# Stepping_Motor_DriverB.net
KiCad netlist of a schematic drawn in Altium Designer
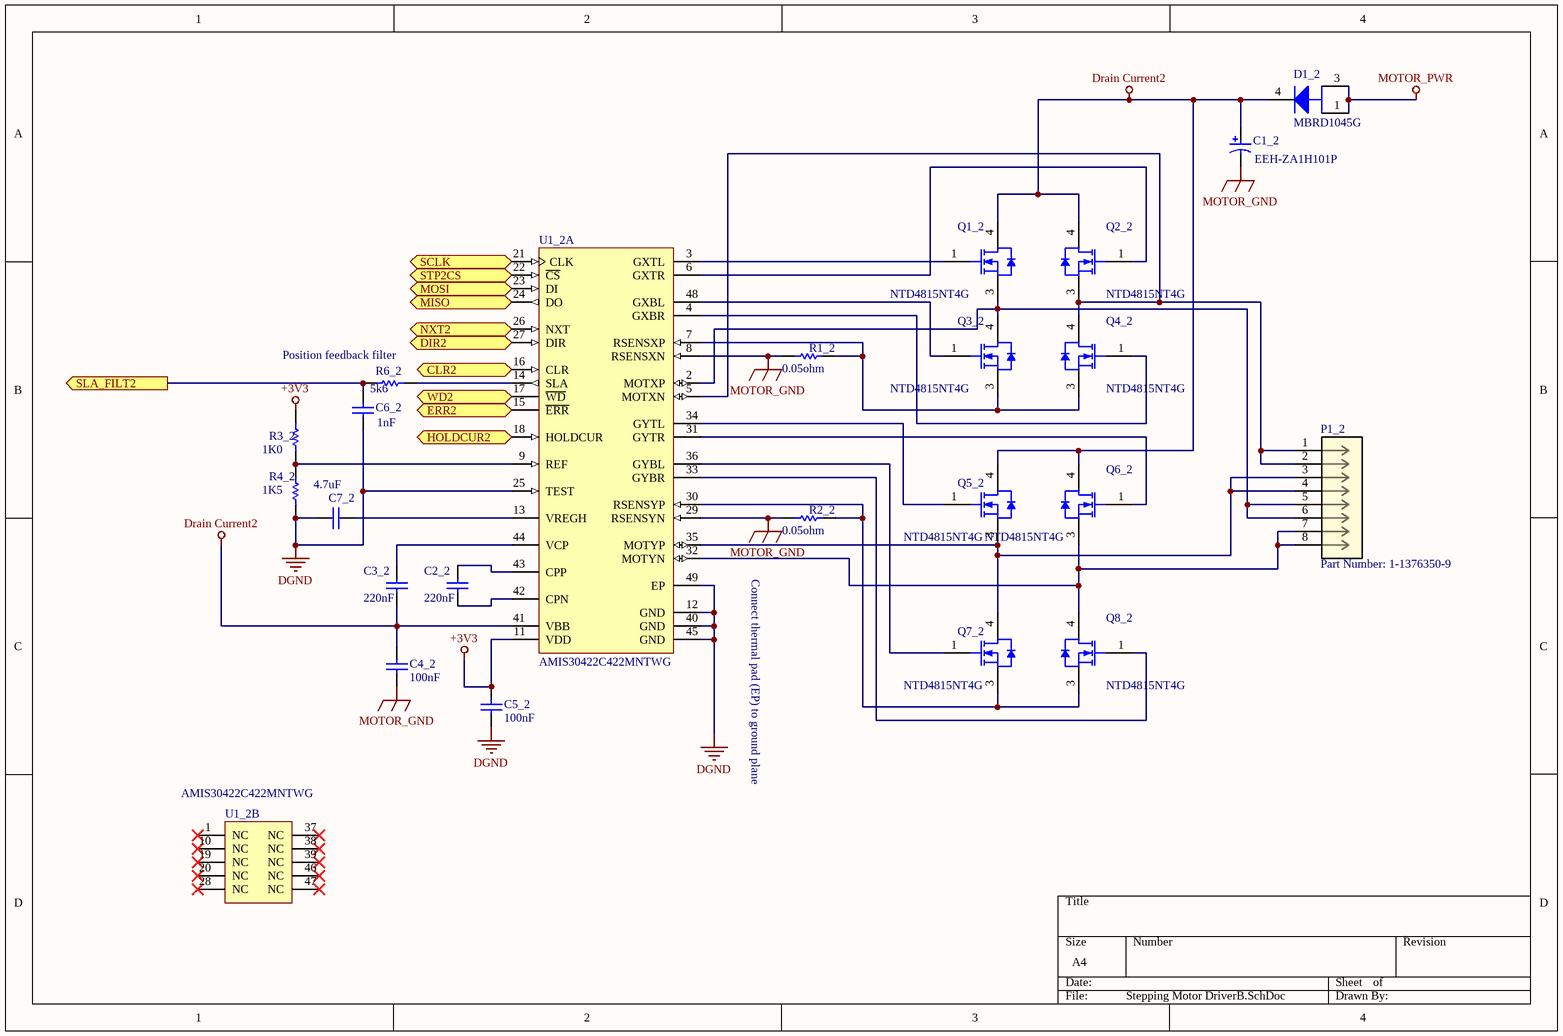
[diagram p0: Stepping Motor DriverB.SchDoc]

(export (version "E")
  (design (tool "Eeschema 10.0.6"))
  (components
    (comp (ref "C1_2")
      (value "EEH-ZA1H101P")
      (footprint "PNSC-ZA-G_L")
      (fields (field (name "TOLERANCE") "20%") (field (name "MANUFACTURER") "Panasonic"))
      (libsource (lib "Altium Content Vault") (part "CAP-P-2"))
    )
    (comp (ref "C2_2")
      (value "220nF")
      (footprint "CAPC0805(2012)75_L")
      (description "CAP 220nF 50V -20% to +80% 0805 (2012 Metric) Thickness 0.75mm SMD")
      (fields (field (name "TOLERANCE") "-20% to +80%") (field (name "Comment") "CAP 220nF 50V 0805(2012)"))
      (libsource (lib "Altium Content Vault") (part "CMP-1036-04556-1"))
    )
    (comp (ref "C3_2")
      (value "220nF")
      (footprint "CAPC0805(2012)75_L")
      (description "CAP 220nF 50V -20% to +80% 0805 (2012 Metric) Thickness 0.75mm SMD")
      (fields (field (name "TOLERANCE") "-20% to +80%") (field (name "Comment") "CAP 220nF 50V 0805(2012)"))
      (libsource (lib "Altium Content Vault") (part "CMP-1036-04556-1"))
    )
    (comp (ref "C4_2")
      (value "100nF")
      (footprint "CAPC1812(4532)110_N")
      (description "CAP 100nF 50V ±20% 1812 (4532 Metric) Thickness 1.1mm SMD")
      (fields (field (name "TOLERANCE") "Â±20%") (field (name "Comment") "CAP 100nF 50V 1812(4532)"))
      (libsource (lib "Altium Content Vault") (part "CMP-1040-01292-1"))
    )
    (comp (ref "C5_2")
      (value "100nF")
      (footprint "CAPC1812(4532)110_N")
      (description "CAP 100nF 50V ±20% 1812 (4532 Metric) Thickness 1.1mm SMD")
      (fields (field (name "TOLERANCE") "Â±20%") (field (name "Comment") "CAP 100nF 50V 1812(4532)"))
      (libsource (lib "Altium Content Vault") (part "CMP-1040-01292-1"))
    )
    (comp (ref "C6_2")
      (value "1nF")
      (footprint "CAPC1206(3216)170_N")
      (description "CAP 1nF 50V ±2% 1206 (3216 Metric) Thickness 1.7mm SMD")
      (fields (field (name "TOLERANCE") "Â±2%") (field (name "Comment") "CAP 1nF 50V 1206(3216)"))
      (libsource (lib "Altium Content Vault") (part "CMP-1037-02447-1"))
    )
    (comp (ref "C7_2")
      (value "4.7uF")
      (footprint "CAPC2220(5750)230_L")
      (description "CAP 4.7uF 50V ±10% 2220 (5750 Metric) Thickness 2.2mm SMD")
      (fields (field (name "TOLERANCE") "Â±10%") (field (name "Comment") "CAP 4.7uF 50V 2220(5750)"))
      (libsource (lib "Altium Content Vault") (part "CMP-1042-00755-1"))
    )
    (comp (ref "D1_2")
      (value "MBRD1045G")
      (footprint "ONSC-DPAK-3-369C-01_V")
      (description "SWITCHMODE(TM) Schottky Power Rectifier, 3-Pin DPAK, Pb-Free, Tube")
      (fields (field (name "MANUFACTURER") "On Semiconductor"))
      (libsource (lib "Altium Content Vault") (part "ONSC-D-A1A3K4-3_A"))
    )
    (comp (ref "P1_2")
      (value "Part Number: 1-1376350-9")
      (footprint "conn8_1-1376350-")
      (description "025 8POS CAP ASSY H TIN")
      (fields
        (field (name "MANUFACTURER_PART_NUMBER") "1-1376350-9")
        (field (name "COPYRIGHT") "Copyright (C) 2018 Accelerated Designs. All rights reserved")
      )
      (libsource (lib "2020-04-08_04-40-03") (part "1-1376350-9"))
    )
    (comp (ref "Q1_2")
      (value "NTD4815NT4G")
      (footprint "ONSC-DPAK-3-369AA-01_V")
      (description "Power MOSFET, 30 V, 35 A, Single N-Channel, 3-Pin DPAK, Pb-Free, Tape and Reel")
      (fields (field (name "MANUFACTURER") "On Semiconductor"))
      (libsource (lib "Altium Content Vault") (part "ONSC-NMOS-G1S3D4-3_B"))
    )
    (comp (ref "Q2_2")
      (value "NTD4815NT4G")
      (footprint "ONSC-DPAK-3-369AA-01_V")
      (description "Power MOSFET, 30 V, 35 A, Single N-Channel, 3-Pin DPAK, Pb-Free, Tape and Reel")
      (fields (field (name "MANUFACTURER") "On Semiconductor"))
      (libsource (lib "Altium Content Vault") (part "CMP-1058-00298-1"))
    )
    (comp (ref "Q3_2")
      (value "NTD4815NT4G")
      (footprint "ONSC-DPAK-3-369AA-01_V")
      (description "Power MOSFET, 30 V, 35 A, Single N-Channel, 3-Pin DPAK, Pb-Free, Tape and Reel")
      (fields (field (name "MANUFACTURER") "On Semiconductor"))
      (libsource (lib "Altium Content Vault") (part "ONSC-NMOS-G1S3D4-3_B"))
    )
    (comp (ref "Q4_2")
      (value "NTD4815NT4G")
      (footprint "ONSC-DPAK-3-369AA-01_V")
      (description "Power MOSFET, 30 V, 35 A, Single N-Channel, 3-Pin DPAK, Pb-Free, Tape and Reel")
      (fields (field (name "MANUFACTURER") "On Semiconductor"))
      (libsource (lib "Altium Content Vault") (part "CMP-1058-00298-1"))
    )
    (comp (ref "Q5_2")
      (value "NTD4815NT4G")
      (footprint "ONSC-DPAK-3-369AA-01_V")
      (description "Power MOSFET, 30 V, 35 A, Single N-Channel, 3-Pin DPAK, Pb-Free, Tape and Reel")
      (fields (field (name "MANUFACTURER") "On Semiconductor"))
      (libsource (lib "Altium Content Vault") (part "ONSC-NMOS-G1S3D4-3_B"))
    )
    (comp (ref "Q6_2")
      (value "NTD4815NT4G")
      (footprint "ONSC-DPAK-3-369AA-01_V")
      (description "Power MOSFET, 30 V, 35 A, Single N-Channel, 3-Pin DPAK, Pb-Free, Tape and Reel")
      (fields (field (name "MANUFACTURER") "On Semiconductor"))
      (libsource (lib "Altium Content Vault") (part "CMP-1058-00298-1"))
    )
    (comp (ref "Q7_2")
      (value "NTD4815NT4G")
      (footprint "ONSC-DPAK-3-369AA-01_V")
      (description "Power MOSFET, 30 V, 35 A, Single N-Channel, 3-Pin DPAK, Pb-Free, Tape and Reel")
      (fields (field (name "MANUFACTURER") "On Semiconductor"))
      (libsource (lib "Altium Content Vault") (part "ONSC-NMOS-G1S3D4-3_B"))
    )
    (comp (ref "Q8_2")
      (value "NTD4815NT4G")
      (footprint "ONSC-DPAK-3-369AA-01_V")
      (description "Power MOSFET, 30 V, 35 A, Single N-Channel, 3-Pin DPAK, Pb-Free, Tape and Reel")
      (fields (field (name "MANUFACTURER") "On Semiconductor"))
      (libsource (lib "Altium Content Vault") (part "CMP-1058-00298-1"))
    )
    (comp (ref "R1_2")
      (value "WSL2512R0500FEA")
      (footprint "RESC6432X89X76LL25T25")
      (description "Chip Resistor, 50 mOhm, +/- 1%, 1 W, -65 to 170 degC, 2512 (6432 Metric), RoHS, Tape and Reel")
      (fields (field (name "MANUFACTURER") "Vishay") (field (name "RESISTANCE") "0.05ohm"))
      (libsource (lib "Altium Content Vault") (part "CMP-2000-07420-1"))
    )
    (comp (ref "R2_2")
      (value "WSL2512R0500FEA")
      (footprint "RESC6432X89X76LL25T25")
      (description "Chip Resistor, 50 mOhm, +/- 1%, 1 W, -65 to 170 degC, 2512 (6432 Metric), RoHS, Tape and Reel")
      (fields (field (name "MANUFACTURER") "Vishay") (field (name "RESISTANCE") "0.05ohm"))
      (libsource (lib "Altium Content Vault") (part "CMP-2000-07420-1"))
    )
    (comp (ref "R3_2")
      (value "1K0")
      (footprint "RESC0805(2012)_M")
      (description "1K 0.125W 1% 0805 (2012 Metric)  SMD")
      (fields (field (name "TOLERANCE") "1 %") (field (name "POWER") "0.125 W"))
      (libsource (lib "Altium Content Vault") (part "CMP-1013-00510-1"))
    )
    (comp (ref "R4_2")
      (value "1K5")
      (footprint "RESC0805(2012)_M")
      (description "1K5 0.125W 1% 0805 (2012 Metric)  SMD")
      (fields (field (name "POWER") "0.125 W") (field (name "TOLERANCE") "1 %"))
      (libsource (lib "Altium Content Vault") (part "CMP-1013-00528-1"))
    )
    (comp (ref "R6_2")
      (value "5k6")
      (footprint "RESC0805(2012)_L")
      (description "5K6 0.125W 1% 0805 (2012 Metric)  SMD")
      (fields (field (name "POWER") "0.125 W") (field (name "TOLERANCE") "1 %"))
      (libsource (lib "Altium Content Vault") (part "CMP-1013-00595-1"))
    )
    (comp (ref "U1_2")
      (value "AMIS30422C422MNTWG")
      (footprint "ONSC-QFN-48-485AJ-01_V")
      (fields (field (name "MANUFACTURER") "ON Semiconductor"))
      (libsource (lib "Altium Content Vault") (part "ONSC-AMIS-30422-QFN-48"))
    )
  )
  (nets
    (net (code "1") (name "+3V3") (class "Default")
      (node (ref "C5_2") (pin "2") (pinfunction "2_2") (pintype "passive"))
      (node (ref "R3_2") (pin "2") (pinfunction "2_2") (pintype "passive"))
      (node (ref "U1_2") (pin "11") (pinfunction "VDD_11") (pintype "power_in"))
    )
    (net (code "2") (name "/CLR2") (class "Default")
      (node (ref "U1_2") (pin "16") (pinfunction "CLR_16") (pintype "input"))
    )
    (net (code "3") (name "/DIR2") (class "Default")
      (node (ref "U1_2") (pin "27") (pinfunction "DIR_27") (pintype "input"))
    )
    (net (code "4") (name "/ERR2") (class "Default")
      (node (ref "U1_2") (pin "15") (pinfunction "~{ERR}_15") (pintype "tri_state"))
    )
    (net (code "5") (name "/HOLDCUR2") (class "Default")
      (node (ref "U1_2") (pin "18") (pinfunction "HOLDCUR_18") (pintype "input"))
    )
    (net (code "6") (name "/MISO") (class "Default")
      (node (ref "U1_2") (pin "24") (pinfunction "DO_24") (pintype "output"))
    )
    (net (code "7") (name "/MOSI") (class "Default")
      (node (ref "U1_2") (pin "23") (pinfunction "DI_23") (pintype "input"))
    )
    (net (code "8") (name "/NXT2") (class "Default")
      (node (ref "U1_2") (pin "26") (pinfunction "NXT_26") (pintype "input"))
    )
    (net (code "9") (name "/SCLK") (class "Default")
      (node (ref "U1_2") (pin "21") (pinfunction "CLK_21") (pintype "input"))
    )
    (net (code "10") (name "/SLA_FILT2") (class "Default")
      (node (ref "C6_2") (pin "2") (pinfunction "2_2") (pintype "passive"))
      (node (ref "R6_2") (pin "1") (pinfunction "1_1") (pintype "passive"))
    )
    (net (code "11") (name "/STP2CS") (class "Default")
      (node (ref "U1_2") (pin "22") (pinfunction "~{CS}_22") (pintype "input"))
    )
    (net (code "12") (name "/WD2") (class "Default")
      (node (ref "U1_2") (pin "17") (pinfunction "~{WD}_17") (pintype "tri_state"))
    )
    (net (code "13") (name "DGND") (class "Default")
      (node (ref "C5_2") (pin "1") (pinfunction "1_1") (pintype "passive"))
      (node (ref "C6_2") (pin "1") (pinfunction "1_1") (pintype "passive"))
      (node (ref "C7_2") (pin "1") (pinfunction "1_1") (pintype "passive"))
      (node (ref "R4_2") (pin "1") (pinfunction "1_1") (pintype "passive"))
      (node (ref "U1_2") (pin "12") (pinfunction "GND_12") (pintype "power_in"))
      (node (ref "U1_2") (pin "25") (pinfunction "TEST_25") (pintype "input"))
      (node (ref "U1_2") (pin "40") (pinfunction "GND_40") (pintype "power_in"))
      (node (ref "U1_2") (pin "45") (pinfunction "GND_45") (pintype "power_in"))
      (node (ref "U1_2") (pin "49") (pinfunction "EP_49") (pintype "passive"))
    )
    (net (code "14") (name "Drain Current2") (class "Default")
      (node (ref "C1_2") (pin "1") (pinfunction "1_1") (pintype "passive"))
      (node (ref "C3_2") (pin "1") (pinfunction "1_1") (pintype "passive"))
      (node (ref "C4_2") (pin "2") (pinfunction "2_2") (pintype "passive"))
      (node (ref "D1_2") (pin "4") (pinfunction "K_4") (pintype "passive"))
      (node (ref "Q1_2") (pin "4") (pinfunction "D_4") (pintype "passive"))
      (node (ref "Q2_2") (pin "4") (pinfunction "D_4") (pintype "passive"))
      (node (ref "Q5_2") (pin "4") (pinfunction "D_4") (pintype "passive"))
      (node (ref "Q6_2") (pin "4") (pinfunction "D_4") (pintype "passive"))
      (node (ref "U1_2") (pin "41") (pinfunction "VBB_41") (pintype "power_in"))
    )
    (net (code "15") (name "MOTOR_GND") (class "Default")
      (node (ref "C1_2") (pin "2") (pinfunction "2_2") (pintype "passive"))
      (node (ref "C4_2") (pin "1") (pinfunction "1_1") (pintype "passive"))
      (node (ref "R1_2") (pin "1") (pinfunction "1_1") (pintype "passive"))
      (node (ref "R2_2") (pin "1") (pinfunction "1_1") (pintype "passive"))
      (node (ref "U1_2") (pin "29") (pinfunction "RSENSYN_29") (pintype "input"))
      (node (ref "U1_2") (pin "8") (pinfunction "RSENSXN_8") (pintype "input"))
    )
    (net (code "16") (name "MOTOR_PWR") (class "Default")
      (node (ref "D1_2") (pin "1") (pinfunction "A_1") (pintype "passive"))
      (node (ref "D1_2") (pin "3") (pinfunction "A_3") (pintype "passive"))
    )
    (net (code "17") (name "Net-(Q1_2-G)") (class "Default")
      (node (ref "Q1_2") (pin "1") (pinfunction "G_1") (pintype "passive"))
      (node (ref "U1_2") (pin "3") (pinfunction "GXTL_3") (pintype "tri_state"))
    )
    (net (code "18") (name "Net-(Q1_2-S)") (class "Default")
      (node (ref "P1_2") (pin "5") (pinfunction "5_5") (pintype "passive"))
      (node (ref "P1_2") (pin "6") (pinfunction "6_6") (pintype "passive"))
      (node (ref "Q1_2") (pin "3") (pinfunction "S_3") (pintype "passive"))
      (node (ref "Q3_2") (pin "4") (pinfunction "D_4") (pintype "passive"))
      (node (ref "U1_2") (pin "2") (pinfunction "MOTXP_2") (pintype "bidirectional"))
    )
    (net (code "19") (name "Net-(Q2_2-G)") (class "Default")
      (node (ref "Q2_2") (pin "1") (pinfunction "G_1") (pintype "passive"))
      (node (ref "U1_2") (pin "6") (pinfunction "GXTR_6") (pintype "tri_state"))
    )
    (net (code "20") (name "Net-(Q2_2-S)") (class "Default")
      (node (ref "P1_2") (pin "1") (pinfunction "1_1") (pintype "passive"))
      (node (ref "P1_2") (pin "2") (pinfunction "2_2") (pintype "passive"))
      (node (ref "Q2_2") (pin "3") (pinfunction "S_3") (pintype "passive"))
      (node (ref "Q4_2") (pin "4") (pinfunction "D_4") (pintype "passive"))
      (node (ref "U1_2") (pin "5") (pinfunction "MOTXN_5") (pintype "bidirectional"))
    )
    (net (code "21") (name "Net-(Q3_2-G)") (class "Default")
      (node (ref "Q3_2") (pin "1") (pinfunction "G_1") (pintype "passive"))
      (node (ref "U1_2") (pin "48") (pinfunction "GXBL_48") (pintype "tri_state"))
    )
    (net (code "22") (name "Net-(Q3_2-S)") (class "Default")
      (node (ref "Q3_2") (pin "3") (pinfunction "S_3") (pintype "passive"))
      (node (ref "Q4_2") (pin "3") (pinfunction "S_3") (pintype "passive"))
      (node (ref "R1_2") (pin "2") (pinfunction "2_2") (pintype "passive"))
      (node (ref "U1_2") (pin "7") (pinfunction "RSENSXP_7") (pintype "input"))
    )
    (net (code "23") (name "Net-(Q4_2-G)") (class "Default")
      (node (ref "Q4_2") (pin "1") (pinfunction "G_1") (pintype "passive"))
      (node (ref "U1_2") (pin "4") (pinfunction "GXBR_4") (pintype "tri_state"))
    )
    (net (code "24") (name "Net-(Q5_2-G)") (class "Default")
      (node (ref "Q5_2") (pin "1") (pinfunction "G_1") (pintype "passive"))
      (node (ref "U1_2") (pin "34") (pinfunction "GYTL_34") (pintype "tri_state"))
    )
    (net (code "25") (name "Net-(Q5_2-S)") (class "Default")
      (node (ref "P1_2") (pin "3") (pinfunction "3_3") (pintype "passive"))
      (node (ref "P1_2") (pin "4") (pinfunction "4_4") (pintype "passive"))
      (node (ref "Q5_2") (pin "3") (pinfunction "S_3") (pintype "passive"))
      (node (ref "Q7_2") (pin "4") (pinfunction "D_4") (pintype "passive"))
      (node (ref "U1_2") (pin "35") (pinfunction "MOTYP_35") (pintype "bidirectional"))
    )
    (net (code "26") (name "Net-(Q6_2-G)") (class "Default")
      (node (ref "Q6_2") (pin "1") (pinfunction "G_1") (pintype "passive"))
      (node (ref "U1_2") (pin "31") (pinfunction "GYTR_31") (pintype "tri_state"))
    )
    (net (code "27") (name "Net-(Q6_2-S)") (class "Default")
      (node (ref "P1_2") (pin "7") (pinfunction "7_7") (pintype "passive"))
      (node (ref "P1_2") (pin "8") (pinfunction "8_8") (pintype "passive"))
      (node (ref "Q6_2") (pin "3") (pinfunction "S_3") (pintype "passive"))
      (node (ref "Q8_2") (pin "4") (pinfunction "D_4") (pintype "passive"))
      (node (ref "U1_2") (pin "32") (pinfunction "MOTYN_32") (pintype "bidirectional"))
    )
    (net (code "28") (name "Net-(Q7_2-G)") (class "Default")
      (node (ref "Q7_2") (pin "1") (pinfunction "G_1") (pintype "passive"))
      (node (ref "U1_2") (pin "36") (pinfunction "GYBL_36") (pintype "tri_state"))
    )
    (net (code "29") (name "Net-(Q7_2-S)") (class "Default")
      (node (ref "Q7_2") (pin "3") (pinfunction "S_3") (pintype "passive"))
      (node (ref "Q8_2") (pin "3") (pinfunction "S_3") (pintype "passive"))
      (node (ref "R2_2") (pin "2") (pinfunction "2_2") (pintype "passive"))
      (node (ref "U1_2") (pin "30") (pinfunction "RSENSYP_30") (pintype "input"))
    )
    (net (code "30") (name "Net-(Q8_2-G)") (class "Default")
      (node (ref "Q8_2") (pin "1") (pinfunction "G_1") (pintype "passive"))
      (node (ref "U1_2") (pin "33") (pinfunction "GYBR_33") (pintype "tri_state"))
    )
    (net (code "31") (name "Net-(U1_2A-CPN)") (class "Default")
      (node (ref "C2_2") (pin "1") (pinfunction "1_1") (pintype "passive"))
      (node (ref "U1_2") (pin "42") (pinfunction "CPN_42") (pintype "passive"))
    )
    (net (code "32") (name "Net-(U1_2A-CPP)") (class "Default")
      (node (ref "C2_2") (pin "2") (pinfunction "2_2") (pintype "passive"))
      (node (ref "U1_2") (pin "43") (pinfunction "CPP_43") (pintype "passive"))
    )
    (net (code "33") (name "Net-(U1_2A-REF)") (class "Default")
      (node (ref "R3_2") (pin "1") (pinfunction "1_1") (pintype "passive"))
      (node (ref "R4_2") (pin "2") (pinfunction "2_2") (pintype "passive"))
      (node (ref "U1_2") (pin "9") (pinfunction "REF_9") (pintype "input"))
    )
    (net (code "34") (name "Net-(U1_2A-SLA)") (class "Default")
      (node (ref "R6_2") (pin "2") (pinfunction "2_2") (pintype "passive"))
      (node (ref "U1_2") (pin "14") (pinfunction "SLA_14") (pintype "output"))
    )
    (net (code "35") (name "Net-(U1_2A-VCP)") (class "Default")
      (node (ref "C3_2") (pin "2") (pinfunction "2_2") (pintype "passive"))
      (node (ref "U1_2") (pin "44") (pinfunction "VCP_44") (pintype "passive"))
    )
    (net (code "36") (name "Net-(U1_2A-VREGH)") (class "Default")
      (node (ref "C7_2") (pin "2") (pinfunction "2_2") (pintype "passive"))
      (node (ref "U1_2") (pin "13") (pinfunction "VREGH_13") (pintype "power_in"))
    )
    (net (code "37") (name "unconnected-(U1_2B-NC-Pad1)") (class "Default")
      (node (ref "U1_2") (pin "1") (pinfunction "NC_1") (pintype "passive+no_connect"))
    )
    (net (code "38") (name "unconnected-(U1_2B-NC-Pad10)") (class "Default")
      (node (ref "U1_2") (pin "10") (pinfunction "NC_10") (pintype "passive+no_connect"))
    )
    (net (code "39") (name "unconnected-(U1_2B-NC-Pad19)") (class "Default")
      (node (ref "U1_2") (pin "19") (pinfunction "NC_19") (pintype "passive+no_connect"))
    )
    (net (code "40") (name "unconnected-(U1_2B-NC-Pad20)") (class "Default")
      (node (ref "U1_2") (pin "20") (pinfunction "NC_20") (pintype "passive+no_connect"))
    )
    (net (code "41") (name "unconnected-(U1_2B-NC-Pad28)") (class "Default")
      (node (ref "U1_2") (pin "28") (pinfunction "NC_28") (pintype "passive+no_connect"))
    )
    (net (code "42") (name "unconnected-(U1_2B-NC-Pad37)") (class "Default")
      (node (ref "U1_2") (pin "37") (pinfunction "NC_37") (pintype "passive+no_connect"))
    )
    (net (code "43") (name "unconnected-(U1_2B-NC-Pad38)") (class "Default")
      (node (ref "U1_2") (pin "38") (pinfunction "NC_38") (pintype "passive+no_connect"))
    )
    (net (code "44") (name "unconnected-(U1_2B-NC-Pad39)") (class "Default")
      (node (ref "U1_2") (pin "39") (pinfunction "NC_39") (pintype "passive+no_connect"))
    )
    (net (code "45") (name "unconnected-(U1_2B-NC-Pad46)") (class "Default")
      (node (ref "U1_2") (pin "46") (pinfunction "NC_46") (pintype "passive+no_connect"))
    )
    (net (code "46") (name "unconnected-(U1_2B-NC-Pad47)") (class "Default")
      (node (ref "U1_2") (pin "47") (pinfunction "NC_47") (pintype "passive+no_connect"))
    )
  )
)
